# MCU_M_V1.net
KiCad netlist of a schematic drawn in Altium Designer
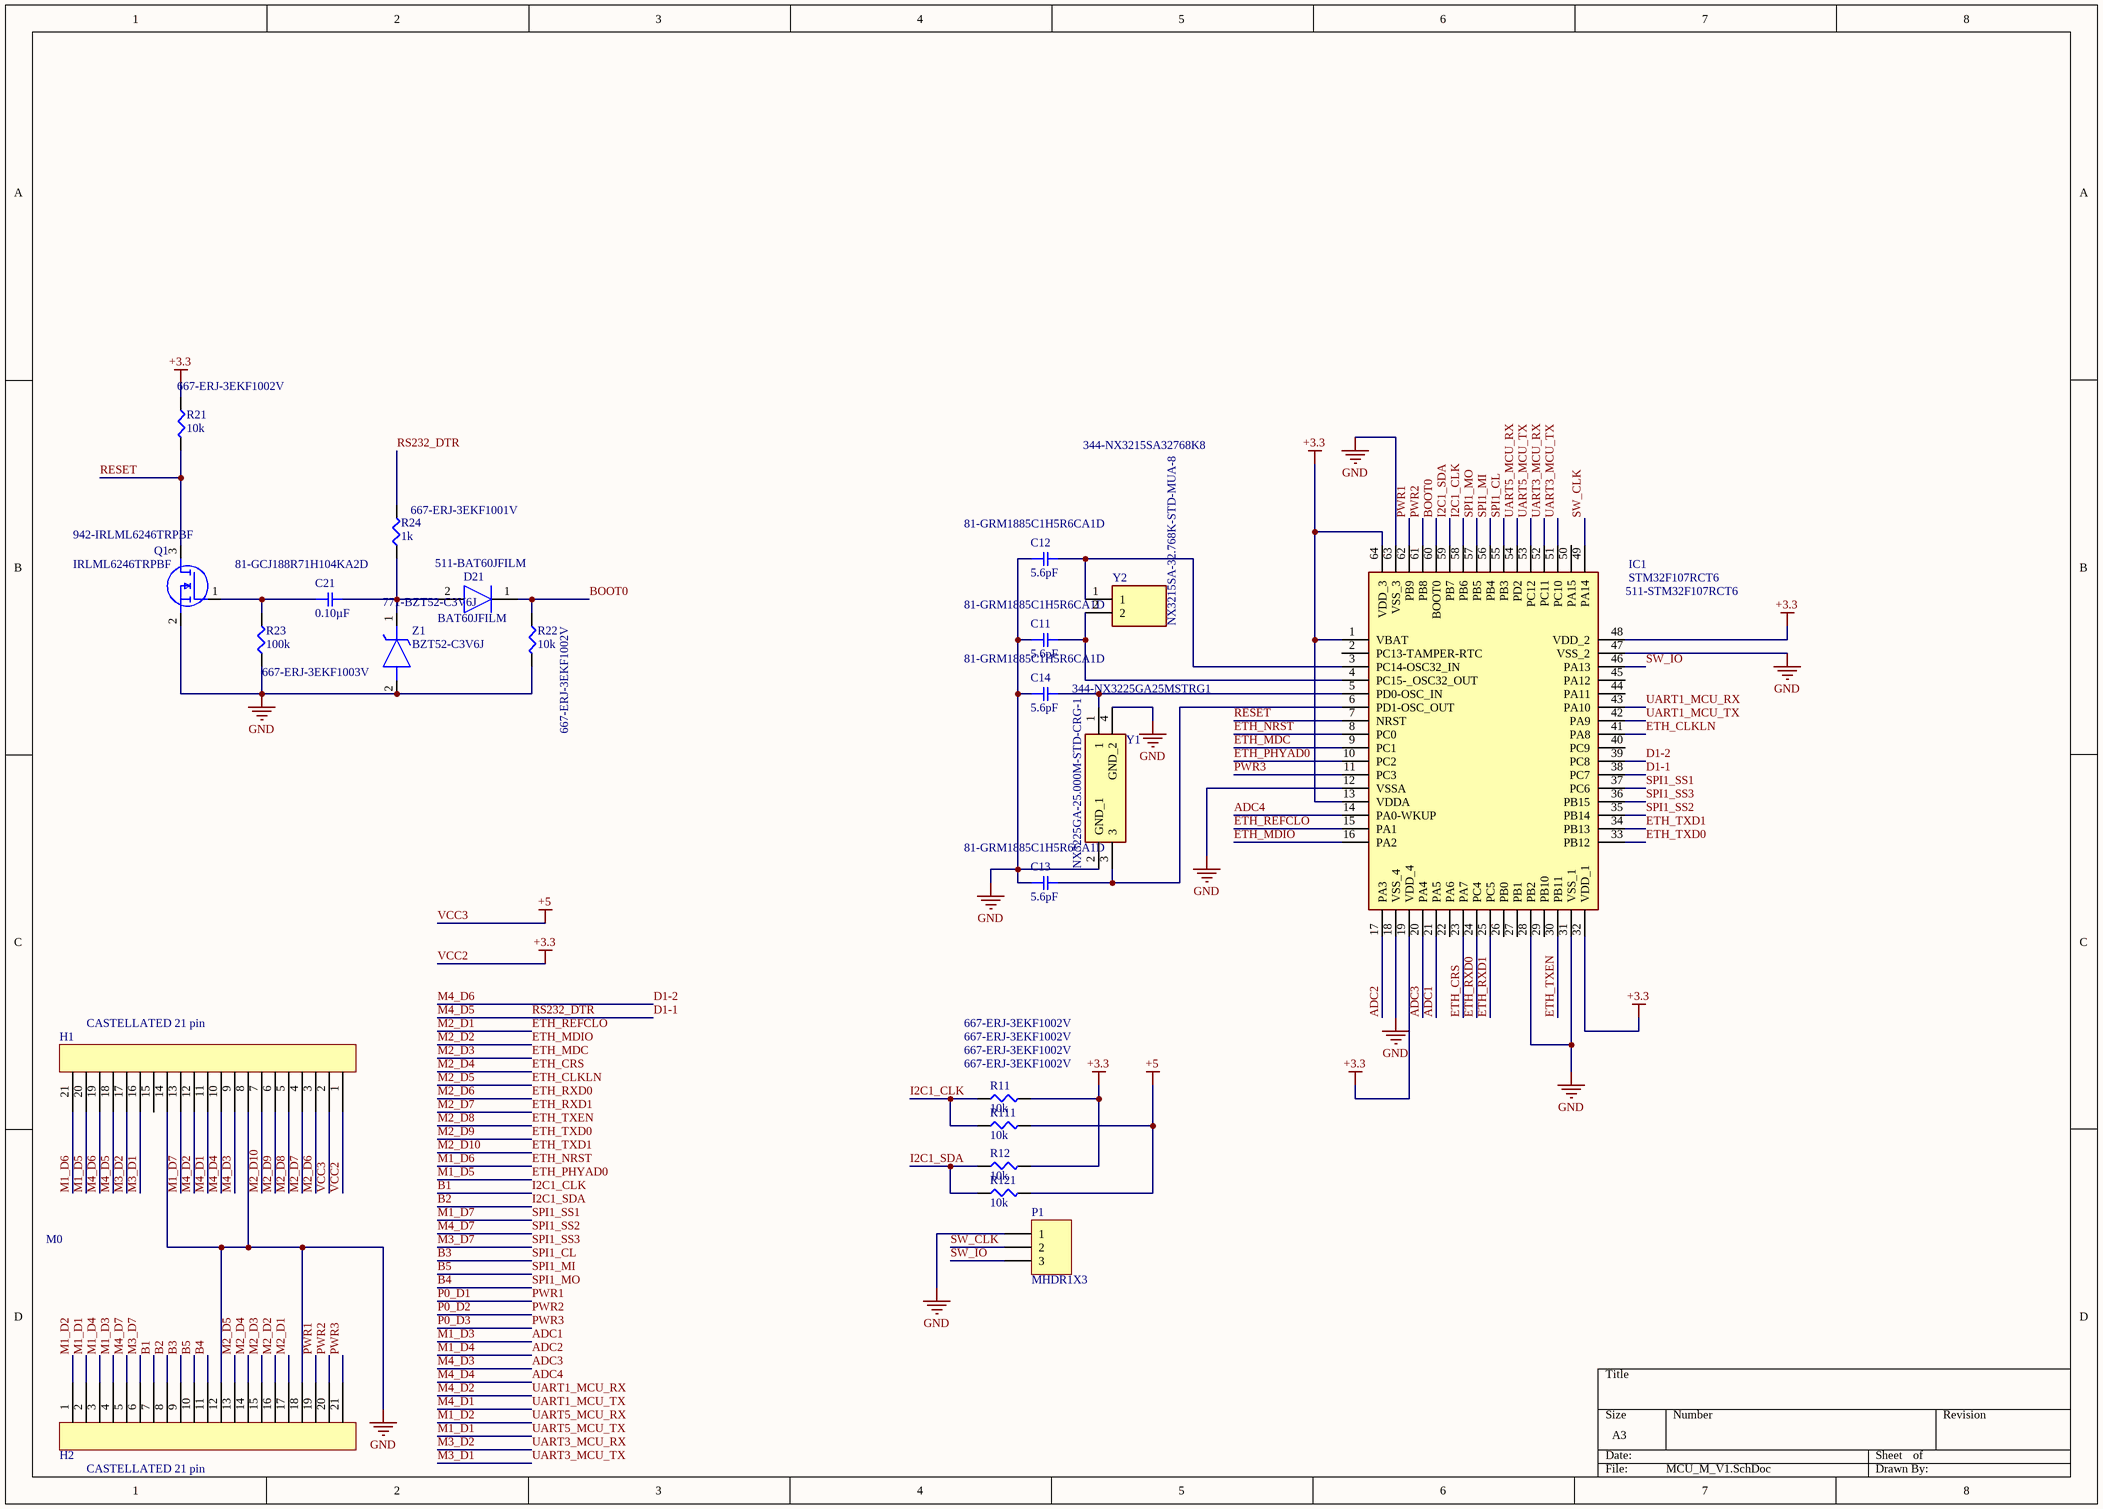
[diagram p0: MCU_M_V1.SchDoc]

(export (version "E")
  (design (tool "Eeschema 10.0.6"))
  (components
    (comp (ref "C11")
      (value "5.6pF")
      (footprint "SMD-0603C")
      (description "CAP CER 5.6PF 50V NP0 0603")
      (fields
        (field (name "DIGI-KEY PART NUMBER") "490-12723-1-ND")
        (field (name "PART NUMBER") "GRM1885C1H5R6CA01D")
        (field (name "SUPPLIER PART NUMBER 1") "81-GRM1885C1H5R6CA1D")
      )
      (libsource (lib "capacitor_murata_0603") (part "GRM1885C1H5R6CA01D"))
    )
    (comp (ref "C12")
      (value "5.6pF")
      (footprint "SMD-0603C")
      (description "CAP CER 5.6PF 50V NP0 0603")
      (fields
        (field (name "DIGI-KEY PART NUMBER") "490-12723-1-ND")
        (field (name "PART NUMBER") "GRM1885C1H5R6CA01D")
        (field (name "SUPPLIER PART NUMBER 1") "81-GRM1885C1H5R6CA1D")
      )
      (libsource (lib "capacitor_murata_0603") (part "GRM1885C1H5R6CA01D"))
    )
    (comp (ref "C13")
      (value "5.6pF")
      (footprint "SMD-0603C")
      (description "CAP CER 5.6PF 50V NP0 0603")
      (fields
        (field (name "DIGI-KEY PART NUMBER") "490-12723-1-ND")
        (field (name "PART NUMBER") "GRM1885C1H5R6CA01D")
        (field (name "SUPPLIER PART NUMBER 1") "81-GRM1885C1H5R6CA1D")
      )
      (libsource (lib "capacitor_murata_0603") (part "GRM1885C1H5R6CA01D"))
    )
    (comp (ref "C14")
      (value "5.6pF")
      (footprint "SMD-0603C")
      (description "CAP CER 5.6PF 50V NP0 0603")
      (fields
        (field (name "DIGI-KEY PART NUMBER") "490-12723-1-ND")
        (field (name "PART NUMBER") "GRM1885C1H5R6CA01D")
        (field (name "SUPPLIER PART NUMBER 1") "81-GRM1885C1H5R6CA1D")
      )
      (libsource (lib "capacitor_murata_0603") (part "GRM1885C1H5R6CA01D"))
    )
    (comp (ref "C21")
      (value "0.10µF")
      (footprint "SMD-0603C")
      (description "CAP CER 0.1UF 50V X7R 0603")
      (fields
        (field (name "DIGI-KEY PART NUMBER") "490-5798-1-ND")
        (field (name "PART NUMBER") "GCJ188R71H104KA12D")
        (field (name "SUPPLIER PART NUMBER 1") "81-GCJ188R71H104KA2D")
      )
      (libsource (lib "capacitor_murata_0603") (part "GCJ188R71H104KA12D"))
    )
    (comp (ref "D21")
      (value "BAT60JFILM")
      (footprint "SamacSys:SOD2513X117N")
      (description "Diode")
      (fields
        (field (name "MOUSER2 PART NUMBER") "511-BAT60JFILM")
        (field (name "SUPPLIER PART NUMBER 1") "511-BAT60JFILM")
      )
      (libsource (lib "*") (part "BAT60JFILM"))
    )
    (comp (ref "H1")
      (value "CASTELLATED 21 pin")
      (footprint "CASTELLATED 21 pin")
      (libsource (lib "") (part "CASTELLATED 21 pin_1"))
    )
    (comp (ref "H2")
      (value "CASTELLATED 21 pin")
      (footprint "CASTELLATED 21 pin")
      (libsource (lib "USIB") (part "CASTELLATED 21 pin"))
    )
    (comp (ref "IC1")
      (value "STM32F107RCT6")
      (footprint "SamacSys:QFP50P1200X1200X160-64N")
      (description "Integrated Circuit")
      (fields
        (field (name "MOUSER2 PART NUMBER") "511-STM32F107RCT6")
        (field (name "SUPPLIER PART NUMBER 1") "511-STM32F107RCT6")
      )
      (libsource (lib "*") (part "STM32F107RCT6"))
    )
    (comp (ref "P1")
      (value "MHDR1X3")
      (footprint "MHDR1X3")
      (description "Header, 3-Pin")
      (fields (field (name "PUBLISHER") "Altium Limited"))
      (libsource (lib "Miscellaneous Connectors") (part "MHDR1X3"))
    )
    (comp (ref "Q1")
      (value "IRLML6246TRPBF")
      (footprint "SamacSys:SOT95P237X112-3N")
      (description "MOSFET (N-Channel)")
      (fields (field (name "SUPPLIER PART NUMBER 1") "942-IRLML6246TRPBF"))
      (libsource (lib "*") (part "IRLML6246TRPBF"))
    )
    (comp (ref "R11")
      (value "10k")
      (footprint "SMD-0603-RES")
      (description "RES SMD 10K OHM 1% 1/10W 0603")
      (fields
        (field (name "PART NUMBER") "ERJ-3EKF1002V")
        (field (name "DIGI-KEY PART NUMBER") "P10.0KHCT-ND")
        (field (name "SUPPLIER PART NUMBER 1") "667-ERJ-3EKF1002V")
      )
      (libsource (lib "Panasonic_ERJ_0603") (part "ERJ-3EKF1002V"))
    )
    (comp (ref "R12")
      (value "10k")
      (footprint "SMD-0603-RES")
      (description "RES SMD 10K OHM 1% 1/10W 0603")
      (fields
        (field (name "PART NUMBER") "ERJ-3EKF1002V")
        (field (name "DIGI-KEY PART NUMBER") "P10.0KHCT-ND")
        (field (name "SUPPLIER PART NUMBER 1") "667-ERJ-3EKF1002V")
      )
      (libsource (lib "Panasonic_ERJ_0603") (part "ERJ-3EKF1002V"))
    )
    (comp (ref "R21")
      (value "10k")
      (footprint "SMD-0603-RES")
      (description "RES SMD 10K OHM 1% 1/10W 0603")
      (fields
        (field (name "PART NUMBER") "ERJ-3EKF1002V")
        (field (name "DIGI-KEY PART NUMBER") "P10.0KHCT-ND")
        (field (name "SUPPLIER PART NUMBER 1") "667-ERJ-3EKF1002V")
      )
      (libsource (lib "Panasonic_ERJ_0603") (part "ERJ-3EKF1002V"))
    )
    (comp (ref "R22")
      (value "10k")
      (footprint "SMD-0603-RES")
      (description "RES SMD 10K OHM 1% 1/10W 0603")
      (fields
        (field (name "PART NUMBER") "ERJ-3EKF1002V")
        (field (name "DIGI-KEY PART NUMBER") "P10.0KHCT-ND")
        (field (name "SUPPLIER PART NUMBER 1") "667-ERJ-3EKF1002V")
      )
      (libsource (lib "Panasonic_ERJ_0603") (part "ERJ-3EKF1002V"))
    )
    (comp (ref "R23")
      (value "100k")
      (footprint "SMD-0603-RES")
      (description "RES SMD 100K OHM 1% 1/10W 0603")
      (fields
        (field (name "PART NUMBER") "ERJ-3EKF1003V")
        (field (name "DIGI-KEY PART NUMBER") "P100KHCT-ND")
        (field (name "SUPPLIER PART NUMBER 1") "667-ERJ-3EKF1003V")
      )
      (libsource (lib "Panasonic_ERJ_0603") (part "ERJ-3EKF1003V"))
    )
    (comp (ref "R24")
      (value "1k")
      (footprint "SMD-0603-RES")
      (description "RES SMD 1K OHM 1% 1/10W 0603")
      (fields
        (field (name "PART NUMBER") "ERJ-3EKF1001V")
        (field (name "DIGI-KEY PART NUMBER") "P1.00KHCT-ND")
        (field (name "SUPPLIER PART NUMBER 1") "667-ERJ-3EKF1001V")
      )
      (libsource (lib "Panasonic_ERJ_0603") (part "ERJ-3EKF1001V"))
    )
    (comp (ref "R111")
      (value "10k")
      (footprint "SMD-0603-RES")
      (description "RES SMD 10K OHM 1% 1/10W 0603")
      (fields
        (field (name "PART NUMBER") "ERJ-3EKF1002V")
        (field (name "DIGI-KEY PART NUMBER") "P10.0KHCT-ND")
        (field (name "SUPPLIER PART NUMBER 1") "667-ERJ-3EKF1002V")
      )
      (libsource (lib "Panasonic_ERJ_0603") (part "ERJ-3EKF1002V"))
    )
    (comp (ref "R121")
      (value "10k")
      (footprint "SMD-0603-RES")
      (description "RES SMD 10K OHM 1% 1/10W 0603")
      (fields
        (field (name "PART NUMBER") "ERJ-3EKF1002V")
        (field (name "DIGI-KEY PART NUMBER") "P10.0KHCT-ND")
        (field (name "SUPPLIER PART NUMBER 1") "667-ERJ-3EKF1002V")
      )
      (libsource (lib "Panasonic_ERJ_0603") (part "ERJ-3EKF1002V"))
    )
    (comp (ref "Y1")
      (value "NX3225GA-25.000M-STD-CRG-1")
      (footprint "SamacSys:NX3225SA_1")
      (description "Crystal or Oscillator")
      (fields
        (field (name "MOUSER2 PART NUMBER") "344-NX3225GA25MSTRG1")
        (field (name "SUPPLIER PART NUMBER 1") "344-NX3225GA25MSTRG1")
      )
      (libsource (lib "*") (part "NX3225GA-25.000M-STD-CRG-1"))
    )
    (comp (ref "Y2")
      (value "NX3215SA-32.768K-STD-MUA-8")
      (footprint "SamacSys:NX3215SA")
      (description "Crystal or Oscillator")
      (fields
        (field (name "MOUSER2 PART NUMBER") "344-NX3215SA32768K8")
        (field (name "SUPPLIER PART NUMBER 1") "344-NX3215SA32768K8")
      )
      (libsource (lib "*") (part "NX3215SA-32.768K-STD-MUA-8"))
    )
    (comp (ref "Z1")
      (value "BZT52-C3V6J")
      (footprint "SamacSys:SOD123")
      (description "Zener Diode")
      (fields
        (field (name "MOUSER2 PART NUMBER") "771-BZT52-C3V6J")
        (field (name "SUPPLIER PART NUMBER 1") "771-BZT52-C3V6J")
      )
      (libsource (lib "*") (part "BZT52-C3V6J"))
    )
  )
  (nets
    (net (code "1") (name "+3.3") (class "Default")
      (node (ref "H1") (pin "1") (pintype "passive"))
      (node (ref "IC1") (pin "1") (pinfunction "VBAT_1") (pintype "passive"))
      (node (ref "IC1") (pin "13") (pinfunction "VDDA_13") (pintype "passive"))
      (node (ref "IC1") (pin "19") (pinfunction "VDD_4_19") (pintype "passive"))
      (node (ref "IC1") (pin "32") (pinfunction "VDD_1_32") (pintype "passive"))
      (node (ref "IC1") (pin "48") (pinfunction "VDD_2_48") (pintype "passive"))
      (node (ref "IC1") (pin "64") (pinfunction "VDD_3_64") (pintype "passive"))
      (node (ref "R11") (pin "2") (pinfunction "2_2") (pintype "passive"))
      (node (ref "R12") (pin "2") (pinfunction "2_2") (pintype "passive"))
      (node (ref "R21") (pin "1") (pinfunction "1_1") (pintype "passive"))
    )
    (net (code "2") (name "+5") (class "Default")
      (node (ref "H1") (pin "2") (pintype "passive"))
      (node (ref "R111") (pin "2") (pinfunction "2_2") (pintype "passive"))
      (node (ref "R121") (pin "2") (pinfunction "2_2") (pintype "passive"))
    )
    (net (code "3") (name "/ADC1") (class "Default")
      (node (ref "H2") (pin "4") (pintype "passive"))
      (node (ref "IC1") (pin "21") (pinfunction "PA5_21") (pintype "passive"))
    )
    (net (code "4") (name "/ADC2") (class "Default")
      (node (ref "H2") (pin "3") (pintype "passive"))
      (node (ref "IC1") (pin "17") (pinfunction "PA3_17") (pintype "passive"))
    )
    (net (code "5") (name "/ADC3") (class "Default")
      (node (ref "H1") (pin "9") (pintype "passive"))
      (node (ref "IC1") (pin "20") (pinfunction "PA4_20") (pintype "passive"))
    )
    (net (code "6") (name "/ADC4") (class "Default")
      (node (ref "H1") (pin "10") (pintype "passive"))
      (node (ref "IC1") (pin "14") (pinfunction "PA0-WKUP_14") (pintype "passive"))
    )
    (net (code "7") (name "/B1") (class "Default")
      (node (ref "H2") (pin "7") (pintype "passive"))
      (node (ref "IC1") (pin "58") (pinfunction "PB6_58") (pintype "passive"))
      (node (ref "R11") (pin "1") (pinfunction "1_1") (pintype "passive"))
      (node (ref "R111") (pin "1") (pinfunction "1_1") (pintype "passive"))
    )
    (net (code "8") (name "/B2") (class "Default")
      (node (ref "H2") (pin "8") (pintype "passive"))
      (node (ref "IC1") (pin "59") (pinfunction "PB7_59") (pintype "passive"))
      (node (ref "R12") (pin "1") (pinfunction "1_1") (pintype "passive"))
      (node (ref "R121") (pin "1") (pinfunction "1_1") (pintype "passive"))
    )
    (net (code "9") (name "/B3") (class "Default")
      (node (ref "H2") (pin "9") (pintype "passive"))
      (node (ref "IC1") (pin "55") (pinfunction "PB3_55") (pintype "passive"))
    )
    (net (code "10") (name "/B4") (class "Default")
      (node (ref "H2") (pin "11") (pintype "passive"))
      (node (ref "IC1") (pin "57") (pinfunction "PB5_57") (pintype "passive"))
    )
    (net (code "11") (name "/B5") (class "Default")
      (node (ref "H2") (pin "10") (pintype "passive"))
      (node (ref "IC1") (pin "56") (pinfunction "PB4_56") (pintype "passive"))
    )
    (net (code "12") (name "/BOOT0") (class "Default")
      (node (ref "D21") (pin "1") (pinfunction "K_1") (pintype "passive"))
      (node (ref "IC1") (pin "60") (pinfunction "BOOT0_60") (pintype "passive"))
      (node (ref "R22") (pin "1") (pinfunction "1_1") (pintype "passive"))
    )
    (net (code "13") (name "/D1-1") (class "Default")
      (node (ref "H1") (pin "18") (pintype "passive"))
      (node (ref "IC1") (pin "38") (pinfunction "PC7_38") (pintype "passive"))
      (node (ref "R24") (pin "2") (pinfunction "2_2") (pintype "passive"))
    )
    (net (code "14") (name "/D1-2") (class "Default")
      (node (ref "H1") (pin "19") (pintype "passive"))
      (node (ref "IC1") (pin "39") (pinfunction "PC8_39") (pintype "passive"))
    )
    (net (code "15") (name "/ETH_CLKLN") (class "Default")
      (node (ref "H2") (pin "13") (pintype "passive"))
      (node (ref "IC1") (pin "41") (pinfunction "PA8_41") (pintype "passive"))
    )
    (net (code "16") (name "/ETH_CRS") (class "Default")
      (node (ref "H2") (pin "14") (pintype "passive"))
      (node (ref "IC1") (pin "23") (pinfunction "PA7_23") (pintype "passive"))
    )
    (net (code "17") (name "/ETH_MDC") (class "Default")
      (node (ref "H2") (pin "15") (pintype "passive"))
      (node (ref "IC1") (pin "9") (pinfunction "PC1_9") (pintype "passive"))
    )
    (net (code "18") (name "/ETH_MDIO") (class "Default")
      (node (ref "H2") (pin "16") (pintype "passive"))
      (node (ref "IC1") (pin "16") (pinfunction "PA2_16") (pintype "passive"))
    )
    (net (code "19") (name "/ETH_NRST") (class "Default")
      (node (ref "H1") (pin "21") (pintype "passive"))
      (node (ref "IC1") (pin "8") (pinfunction "PC0_8") (pintype "passive"))
    )
    (net (code "20") (name "/ETH_PHYAD0") (class "Default")
      (node (ref "H1") (pin "20") (pintype "passive"))
      (node (ref "IC1") (pin "10") (pinfunction "PC2_10") (pintype "passive"))
    )
    (net (code "21") (name "/ETH_REFCLO") (class "Default")
      (node (ref "H2") (pin "17") (pintype "passive"))
      (node (ref "IC1") (pin "15") (pinfunction "PA1_15") (pintype "passive"))
    )
    (net (code "22") (name "/ETH_RXD0") (class "Default")
      (node (ref "H1") (pin "3") (pintype "passive"))
      (node (ref "IC1") (pin "24") (pinfunction "PC4_24") (pintype "passive"))
    )
    (net (code "23") (name "/ETH_RXD1") (class "Default")
      (node (ref "H1") (pin "4") (pintype "passive"))
      (node (ref "IC1") (pin "25") (pinfunction "PC5_25") (pintype "passive"))
    )
    (net (code "24") (name "/ETH_TXD0") (class "Default")
      (node (ref "H1") (pin "6") (pintype "passive"))
      (node (ref "IC1") (pin "33") (pinfunction "PB12_33") (pintype "passive"))
    )
    (net (code "25") (name "/ETH_TXD1") (class "Default")
      (node (ref "H1") (pin "7") (pintype "passive"))
      (node (ref "IC1") (pin "34") (pinfunction "PB13_34") (pintype "passive"))
    )
    (net (code "26") (name "/ETH_TXEN") (class "Default")
      (node (ref "H1") (pin "5") (pintype "passive"))
      (node (ref "IC1") (pin "30") (pinfunction "PB11_30") (pintype "passive"))
    )
    (net (code "27") (name "/M1_D1") (class "Default")
      (node (ref "H2") (pin "2") (pintype "passive"))
      (node (ref "IC1") (pin "53") (pinfunction "PC12_53") (pintype "passive"))
    )
    (net (code "28") (name "/M1_D2") (class "Default")
      (node (ref "H2") (pin "1") (pintype "passive"))
      (node (ref "IC1") (pin "54") (pinfunction "PD2_54") (pintype "passive"))
    )
    (net (code "29") (name "/M1_D7") (class "Default")
      (node (ref "H1") (pin "13") (pintype "passive"))
      (node (ref "IC1") (pin "37") (pinfunction "PC6_37") (pintype "passive"))
    )
    (net (code "30") (name "/M3_D1") (class "Default")
      (node (ref "H1") (pin "16") (pintype "passive"))
      (node (ref "IC1") (pin "51") (pinfunction "PC10_51") (pintype "passive"))
    )
    (net (code "31") (name "/M3_D2") (class "Default")
      (node (ref "H1") (pin "17") (pintype "passive"))
      (node (ref "IC1") (pin "52") (pinfunction "PC11_52") (pintype "passive"))
    )
    (net (code "32") (name "/M3_D7") (class "Default")
      (node (ref "H2") (pin "6") (pintype "passive"))
      (node (ref "IC1") (pin "36") (pinfunction "PB15_36") (pintype "passive"))
    )
    (net (code "33") (name "/M4_D1") (class "Default")
      (node (ref "H1") (pin "11") (pintype "passive"))
      (node (ref "IC1") (pin "42") (pinfunction "PA9_42") (pintype "passive"))
    )
    (net (code "34") (name "/M4_D2") (class "Default")
      (node (ref "H1") (pin "12") (pintype "passive"))
      (node (ref "IC1") (pin "43") (pinfunction "PA10_43") (pintype "passive"))
    )
    (net (code "35") (name "/M4_D7") (class "Default")
      (node (ref "H2") (pin "5") (pintype "passive"))
      (node (ref "IC1") (pin "35") (pinfunction "PB14_35") (pintype "passive"))
    )
    (net (code "36") (name "/P0_D1") (class "Default")
      (node (ref "H2") (pin "19") (pintype "passive"))
      (node (ref "IC1") (pin "62") (pinfunction "PB9_62") (pintype "passive"))
    )
    (net (code "37") (name "/P0_D2") (class "Default")
      (node (ref "H2") (pin "20") (pintype "passive"))
      (node (ref "IC1") (pin "61") (pinfunction "PB8_61") (pintype "passive"))
    )
    (net (code "38") (name "/P0_D3") (class "Default")
      (node (ref "H2") (pin "21") (pintype "passive"))
      (node (ref "IC1") (pin "11") (pinfunction "PC3_11") (pintype "passive"))
    )
    (net (code "39") (name "/RESET") (class "Default")
      (node (ref "IC1") (pin "7") (pinfunction "NRST_7") (pintype "passive"))
      (node (ref "Q1") (pin "3") (pinfunction "D_3") (pintype "passive"))
      (node (ref "R21") (pin "2") (pinfunction "2_2") (pintype "passive"))
    )
    (net (code "40") (name "/SW_CLK") (class "Default")
      (node (ref "IC1") (pin "49") (pinfunction "PA14_49") (pintype "passive"))
      (node (ref "P1") (pin "2") (pinfunction "2_2") (pintype "passive"))
    )
    (net (code "41") (name "/SW_IO") (class "Default")
      (node (ref "IC1") (pin "46") (pinfunction "PA13_46") (pintype "passive"))
      (node (ref "P1") (pin "3") (pinfunction "3_3") (pintype "passive"))
    )
    (net (code "42") (name "GND") (class "Default")
      (node (ref "C11") (pin "1") (pinfunction "1_1") (pintype "passive"))
      (node (ref "C12") (pin "1") (pinfunction "1_1") (pintype "passive"))
      (node (ref "C13") (pin "1") (pinfunction "1_1") (pintype "passive"))
      (node (ref "C14") (pin "1") (pinfunction "1_1") (pintype "passive"))
      (node (ref "H1") (pin "14") (pintype "passive"))
      (node (ref "H1") (pin "8") (pintype "passive"))
      (node (ref "H2") (pin "12") (pintype "passive"))
      (node (ref "H2") (pin "18") (pintype "passive"))
      (node (ref "IC1") (pin "12") (pinfunction "VSSA_12") (pintype "passive"))
      (node (ref "IC1") (pin "18") (pinfunction "VSS_4_18") (pintype "passive"))
      (node (ref "IC1") (pin "28") (pinfunction "PB2_28") (pintype "passive"))
      (node (ref "IC1") (pin "31") (pinfunction "VSS_1_31") (pintype "passive"))
      (node (ref "IC1") (pin "47") (pinfunction "VSS_2_47") (pintype "passive"))
      (node (ref "IC1") (pin "63") (pinfunction "VSS_3_63") (pintype "passive"))
      (node (ref "P1") (pin "1") (pinfunction "1_1") (pintype "passive"))
      (node (ref "Q1") (pin "2") (pinfunction "S_2") (pintype "passive"))
      (node (ref "R22") (pin "2") (pinfunction "2_2") (pintype "passive"))
      (node (ref "R23") (pin "1") (pinfunction "1_1") (pintype "passive"))
      (node (ref "Y1") (pin "2") (pinfunction "GND_1_2") (pintype "passive"))
      (node (ref "Y1") (pin "4") (pinfunction "GND_2_4") (pintype "passive"))
      (node (ref "Z1") (pin "2") (pinfunction "A_2") (pintype "passive"))
    )
    (net (code "43") (name "Net-(D21-A)") (class "Default")
      (node (ref "C21") (pin "2") (pinfunction "2_2") (pintype "passive"))
      (node (ref "D21") (pin "2") (pinfunction "A_2") (pintype "passive"))
      (node (ref "R24") (pin "1") (pinfunction "1_1") (pintype "passive"))
      (node (ref "Z1") (pin "1") (pinfunction "K_1") (pintype "passive"))
    )
    (net (code "44") (name "Net-(IC1-PC14-OSC32_IN)") (class "Default")
      (node (ref "C12") (pin "2") (pinfunction "2_2") (pintype "passive"))
      (node (ref "IC1") (pin "3") (pinfunction "PC14-OSC32_IN_3") (pintype "passive"))
      (node (ref "Y2") (pin "1") (pinfunction "1_1") (pintype "passive"))
    )
    (net (code "45") (name "Net-(IC1-PC15-_OSC32_OUT)") (class "Default")
      (node (ref "C11") (pin "2") (pinfunction "2_2") (pintype "passive"))
      (node (ref "IC1") (pin "4") (pinfunction "PC15-_OSC32_OUT_4") (pintype "passive"))
      (node (ref "Y2") (pin "2") (pinfunction "2_2") (pintype "passive"))
    )
    (net (code "46") (name "Net-(IC1-PD0-OSC_IN)") (class "Default")
      (node (ref "C14") (pin "2") (pinfunction "2_2") (pintype "passive"))
      (node (ref "IC1") (pin "5") (pinfunction "PD0-OSC_IN_5") (pintype "passive"))
      (node (ref "Y1") (pin "1") (pinfunction "1_1") (pintype "passive"))
    )
    (net (code "47") (name "Net-(IC1-PD1-OSC_OUT)") (class "Default")
      (node (ref "C13") (pin "2") (pinfunction "2_2") (pintype "passive"))
      (node (ref "IC1") (pin "6") (pinfunction "PD1-OSC_OUT_6") (pintype "passive"))
      (node (ref "Y1") (pin "3") (pinfunction "3_3") (pintype "passive"))
    )
    (net (code "48") (name "Net-(Q1-G)") (class "Default")
      (node (ref "C21") (pin "1") (pinfunction "1_1") (pintype "passive"))
      (node (ref "Q1") (pin "1") (pinfunction "G_1") (pintype "passive"))
      (node (ref "R23") (pin "2") (pinfunction "2_2") (pintype "passive"))
    )
    (net (code "49") (name "unconnected-(H1-Pad15)") (class "Default")
      (node (ref "H1") (pin "15") (pintype "passive"))
    )
    (net (code "50") (name "unconnected-(IC1-PA6-Pad22)") (class "Default")
      (node (ref "IC1") (pin "22") (pinfunction "PA6_22") (pintype "passive"))
    )
    (net (code "51") (name "unconnected-(IC1-PA11-Pad44)") (class "Default")
      (node (ref "IC1") (pin "44") (pinfunction "PA11_44") (pintype "passive"))
    )
    (net (code "52") (name "unconnected-(IC1-PA12-Pad45)") (class "Default")
      (node (ref "IC1") (pin "45") (pinfunction "PA12_45") (pintype "passive"))
    )
    (net (code "53") (name "unconnected-(IC1-PA15-Pad50)") (class "Default")
      (node (ref "IC1") (pin "50") (pinfunction "PA15_50") (pintype "passive"))
    )
    (net (code "54") (name "unconnected-(IC1-PB0-Pad26)") (class "Default")
      (node (ref "IC1") (pin "26") (pinfunction "PB0_26") (pintype "passive"))
    )
    (net (code "55") (name "unconnected-(IC1-PB1-Pad27)") (class "Default")
      (node (ref "IC1") (pin "27") (pinfunction "PB1_27") (pintype "passive"))
    )
    (net (code "56") (name "unconnected-(IC1-PB10-Pad29)") (class "Default")
      (node (ref "IC1") (pin "29") (pinfunction "PB10_29") (pintype "passive"))
    )
    (net (code "57") (name "unconnected-(IC1-PC9-Pad40)") (class "Default")
      (node (ref "IC1") (pin "40") (pinfunction "PC9_40") (pintype "passive"))
    )
    (net (code "58") (name "unconnected-(IC1-PC13-TAMPER-RTC-Pad2)") (class "Default")
      (node (ref "IC1") (pin "2") (pinfunction "PC13-TAMPER-RTC_2") (pintype "passive"))
    )
  )
)
